# 5V_Switching_Reg.net
KiCad netlist of a schematic drawn in Altium Designer
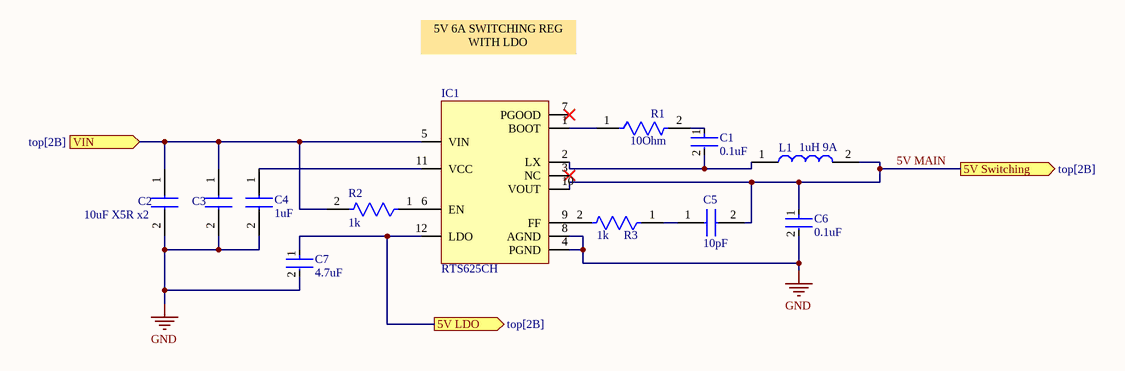
[diagram p0: 5V Switching Reg.SchDoc]

(export (version "E")
  (design (tool "Eeschema 10.0.6"))
  (components
    (comp (ref "C1")
      (value "0.1uF")
      (footprint "FP-C0603C-CF-MFG")
      (description "CAP CER 0.1UF 25V X7R 0603")
      (fields
        (field (name "MANUFACTURER PART NUMBER") "C0603C104K3RACTU")
        (field (name "OCTOPART") "https://octopart.com/c0603c104k3ractu-kemet-127541")
      )
      (libsource (lib "Altium Content Vault") (part "b4654b650e69147ec39a6b967a45e02"))
    )
    (comp (ref "C2")
      (value "10uF X5R x2")
      (footprint "SamacSys:CAPC1608X90N")
      (description "Capacitor")
      (fields
        (field (name "MANUFACTURER_PART_NUMBER") "CL10A106MA8NRNC")
        (field (name "MOUSER PART NUMBER") "187-CL10A106MA8NRNC")
      )
      (libsource (lib "*") (part "CL10A106MA8NRNC"))
    )
    (comp (ref "C3")
      (value "10uF X5R")
      (footprint "SamacSys:CAPC1608X90N")
      (description "Capacitor")
      (fields
        (field (name "MANUFACTURER_PART_NUMBER") "CL10A106MA8NRNC")
        (field (name "MOUSER PART NUMBER") "187-CL10A106MA8NRNC")
      )
      (libsource (lib "*") (part "CL10A106MA8NRNC"))
    )
    (comp (ref "C4")
      (value "1uF")
      (footprint "SamacSys:CAPC1608X90N")
      (description "Capacitor")
      (fields
        (field (name "MANUFACTURER_PART_NUMBER") "EMK107B7105KA-T")
        (field (name "MOUSER PART NUMBER") "963-EMK107B7105KA-T")
      )
      (libsource (lib "*") (part "EMK107B7105KA-T"))
    )
    (comp (ref "C5")
      (value "10pF")
      (footprint "SamacSys:CAPC1608X95N")
      (description "Capacitor")
      (fields
        (field (name "MANUFACTURER_PART_NUMBER") "0603N100J500CT")
        (field (name "MOUSER PART NUMBER") "791-0603N100J500CT")
      )
      (libsource (lib "*") (part "0603N100J500CT"))
    )
    (comp (ref "C6")
      (value "0.1uF")
      (footprint "FP-C0603C-CF-MFG")
      (description "CAP CER 0.1UF 25V X7R 0603")
      (fields
        (field (name "MANUFACTURER PART NUMBER") "C0603C104K3RACTU")
        (field (name "OCTOPART") "https://octopart.com/c0603c104k3ractu-kemet-127541")
      )
      (libsource (lib "Altium Content Vault") (part "b4654b650e69147ec39a6b967a45e02"))
    )
    (comp (ref "C7")
      (value "4.7uF")
      (footprint "FP-CL10-IPC_C")
      (description "Cap Ceramic 4.7uF 10V X5R ±10% Pad SMD 0603 +85°C T/R")
      (fields (field (name "TOLERANCE") "10%"))
      (libsource (lib "Altium Content Vault") (part "b4654b650e69147ec39a6b967a45e02"))
    )
    (comp (ref "IC1")
      (value "RTS625CH")
      (footprint "RT6258C")
      (description "5V6A SWITCHING REG WITH 5V LDO")
      (libsource (lib "RT6256CH") (part "RTS625CH"))
    )
    (comp (ref "L1")
      (value "1uH 9A")
      (footprint "SamacSys:IFDC3030EZER1R0N")
      (description "Inductor")
      (fields
        (field (name "MANUFACTURER_PART_NUMBER") "IFDC3030EZER1R0N")
        (field (name "MOUSER PART NUMBER") "70-IFDC3030EZER1R0N")
      )
      (libsource (lib "*") (part "IFDC3030EZER1R0N"))
    )
    (comp (ref "R1")
      (value "10Ohm")
      (footprint "FP-CRCW0603-C-MFG")
      (description "RES SMD 10 OHM 1% 1/10W 0603")
      (fields (field (name "TOLERANCE") "1%"))
      (libsource (lib "Altium Content Vault") (part "1029c3af85768c4190bb7ad29bc67b5"))
    )
    (comp (ref "R2")
      (value "1k")
      (footprint "FP-RC0603-0_55-IPC_C")
      (description "RES 1K OHM 1% 1/10W 0603")
      (fields (field (name "TOLERANCE") "1%"))
      (libsource (lib "Altium Content Vault") (part "1029c3af85768c4190bb7ad29bc67b5"))
    )
    (comp (ref "R3")
      (value "1k")
      (footprint "FP-RC0603-0_55-IPC_C")
      (description "RES 1K OHM 1% 1/10W 0603")
      (fields (field (name "TOLERANCE") "1%"))
      (libsource (lib "Altium Content Vault") (part "1029c3af85768c4190bb7ad29bc67b5"))
    )
  )
  (nets
    (net (code "1") (name "/5V LDO") (class "Default")
      (node (ref "C7") (pin "1") (pinfunction "1_1") (pintype "passive"))
      (node (ref "IC1") (pin "12") (pinfunction "LDO_12") (pintype "passive"))
    )
    (net (code "2") (name "/5V MAIN") (class "Default")
      (node (ref "C5") (pin "2") (pinfunction "2_2") (pintype "passive"))
      (node (ref "C6") (pin "1") (pinfunction "1_1") (pintype "passive"))
      (node (ref "IC1") (pin "10") (pinfunction "VOUT_10") (pintype "passive"))
      (node (ref "L1") (pin "2") (pinfunction "2_2") (pintype "passive"))
    )
    (net (code "3") (name "/VIN") (class "Default")
      (node (ref "C2") (pin "1") (pinfunction "1_1") (pintype "passive"))
      (node (ref "C3") (pin "1") (pinfunction "1_1") (pintype "passive"))
      (node (ref "IC1") (pin "5") (pinfunction "VIN_5") (pintype "passive"))
      (node (ref "R2") (pin "2") (pinfunction "2_2") (pintype "passive"))
    )
    (net (code "4") (name "GND") (class "Default")
      (node (ref "C2") (pin "2") (pinfunction "2_2") (pintype "passive"))
      (node (ref "C3") (pin "2") (pinfunction "2_2") (pintype "passive"))
      (node (ref "C4") (pin "2") (pinfunction "2_2") (pintype "passive"))
      (node (ref "C6") (pin "2") (pinfunction "2_2") (pintype "passive"))
      (node (ref "C7") (pin "2") (pinfunction "2_2") (pintype "passive"))
      (node (ref "IC1") (pin "4") (pinfunction "PGND_4") (pintype "passive"))
      (node (ref "IC1") (pin "8") (pinfunction "AGND_8") (pintype "passive"))
    )
    (net (code "5") (name "Net-(C1-Pad1)") (class "Default")
      (node (ref "C1") (pin "1") (pinfunction "1_1") (pintype "passive"))
      (node (ref "R1") (pin "2") (pinfunction "2_2") (pintype "passive"))
    )
    (net (code "6") (name "Net-(C5-Pad1)") (class "Default")
      (node (ref "C5") (pin "1") (pinfunction "1_1") (pintype "passive"))
      (node (ref "R3") (pin "1") (pinfunction "1_1") (pintype "passive"))
    )
    (net (code "7") (name "Net-(IC1-BOOT)") (class "Default")
      (node (ref "IC1") (pin "1") (pinfunction "BOOT_1") (pintype "passive"))
      (node (ref "R1") (pin "1") (pinfunction "1_1") (pintype "passive"))
    )
    (net (code "8") (name "Net-(IC1-EN)") (class "Default")
      (node (ref "IC1") (pin "6") (pinfunction "EN_6") (pintype "passive"))
      (node (ref "R2") (pin "1") (pinfunction "1_1") (pintype "passive"))
    )
    (net (code "9") (name "Net-(IC1-FF)") (class "Default")
      (node (ref "IC1") (pin "9") (pinfunction "FF_9") (pintype "passive"))
      (node (ref "R3") (pin "2") (pinfunction "2_2") (pintype "passive"))
    )
    (net (code "10") (name "Net-(IC1-LX)") (class "Default")
      (node (ref "C1") (pin "2") (pinfunction "2_2") (pintype "passive"))
      (node (ref "IC1") (pin "2") (pinfunction "LX_2") (pintype "passive"))
      (node (ref "L1") (pin "1") (pinfunction "1_1") (pintype "passive"))
    )
    (net (code "11") (name "Net-(IC1-VCC)") (class "Default")
      (node (ref "C4") (pin "1") (pinfunction "1_1") (pintype "passive"))
      (node (ref "IC1") (pin "11") (pinfunction "VCC_11") (pintype "passive"))
    )
    (net (code "12") (name "unconnected-(IC1-NC-Pad3)") (class "Default")
      (node (ref "IC1") (pin "3") (pinfunction "NC_3") (pintype "passive+no_connect"))
    )
    (net (code "13") (name "unconnected-(IC1-PGOOD-Pad7)") (class "Default")
      (node (ref "IC1") (pin "7") (pinfunction "PGOOD_7") (pintype "passive+no_connect"))
    )
  )
)
